# TPT02rrrrrr.net
KiCad netlist of a schematic drawn in EAGLE
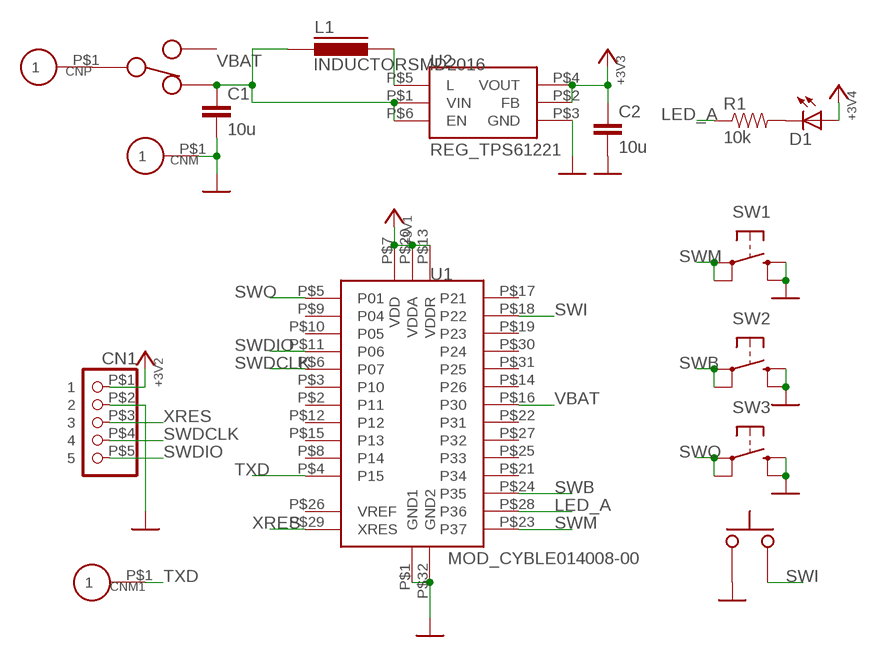
[diagram p0: schematic, sheet 1]

(export (version "E")
  (design (tool "Eeschema 10.0.6"))
  (components
    (comp (ref "C1")
      (value "10u")
      (footprint "eagle-import:0603")
      (libsource (lib "eagle-import") (part "CAP0603"))
    )
    (comp (ref "C2")
      (value "10u")
      (footprint "eagle-import:0603")
      (libsource (lib "eagle-import") (part "CAP0603"))
    )
    (comp (ref "CN1")
      (value "CON_PINHD-1X550MIL")
      (footprint "eagle-import:1X5_50MIL")
      (libsource (lib "eagle-import") (part "CON_PINHD-1X550MIL"))
    )
    (comp (ref "CNM")
      (value "CON_P01SMD1MM")
      (footprint "eagle-import:PAD_SMD1MM")
      (libsource (lib "eagle-import") (part "CON_P01SMD1MM"))
    )
    (comp (ref "CNM1")
      (value "CON_P01SMD1MM")
      (footprint "eagle-import:PAD_SMD1MM")
      (libsource (lib "eagle-import") (part "CON_P01SMD1MM"))
    )
    (comp (ref "CNP")
      (value "CON_P01SMD1MM")
      (footprint "eagle-import:PAD_SMD1MM")
      (libsource (lib "eagle-import") (part "CON_P01SMD1MM"))
    )
    (comp (ref "D1")
      (value "LED0603")
      (footprint "eagle-import:SPARKFUN_LED-0603")
      (libsource (lib "eagle-import") (part "LED0603"))
    )
    (comp (ref "L1")
      (value "INDUCTORSMD2016")
      (footprint "eagle-import:2016")
      (libsource (lib "eagle-import") (part "INDUCTORSMD2016"))
    )
    (comp (ref "R1")
      (value "10k")
      (footprint "eagle-import:0603")
      (libsource (lib "eagle-import") (part "RES0603"))
    )
    (comp (ref "SW1")
      (value "SW_TACTEVQP2")
      (footprint "eagle-import:SW_EVQP2")
      (libsource (lib "eagle-import") (part "SW_TACTEVQP2"))
    )
    (comp (ref "SW2")
      (value "SW_TACTEVQPLNA08NOGND")
      (footprint "eagle-import:SW_EVQPLBA08_NOGND")
      (libsource (lib "eagle-import") (part "SW_TACTEVQPLNA08NOGND"))
    )
    (comp (ref "SW3")
      (value "SW_TACTEVQPLNA08NOGND")
      (footprint "eagle-import:SW_EVQPLBA08_NOGND")
      (libsource (lib "eagle-import") (part "SW_TACTEVQPLNA08NOGND"))
    )
    (comp (ref "SW4")
      (value "SW_SLIDECUS12B")
      (footprint "eagle-import:SW_CUS-12B")
      (libsource (lib "eagle-import") (part "SW_SLIDECUS12B"))
    )
    (comp (ref "SW5")
      (value "SW_TACT2PB3U3000")
      (footprint "eagle-import:SW_B3U-3000P")
      (libsource (lib "eagle-import") (part "SW_TACT2PB3U3000"))
    )
    (comp (ref "U1")
      (value "MOD_CYBLE014008-00")
      (footprint "eagle-import:MOD_CYBLE014008-00")
      (libsource (lib "eagle-import") (part "MOD_CYBLE014008-00"))
    )
    (comp (ref "U2")
      (value "REG_TPS61221")
      (footprint "eagle-import:SC70-6")
      (libsource (lib "eagle-import") (part "REG_TPS61221"))
    )
  )
  (nets
    (net (code "1") (name "/LED_A") (class "Default")
      (node (ref "R1") (pin "1") (pinfunction "1_1") (pintype "passive"))
      (node (ref "U1") (pin "P$28") (pinfunction "P36_P$28") (pintype "bidirectional"))
    )
    (net (code "2") (name "/P$3") (class "Default")
      (node (ref "SW4") (pin "P$3") (pinfunction "P$3_P$3") (pintype "power_in"))
    )
    (net (code "3") (name "/SWB") (class "Default")
      (node (ref "SW2") (pin "A1") (pinfunction "P_A1") (pintype "passive"))
      (node (ref "SW2") (pin "A2") (pinfunction "P1_A2") (pintype "passive"))
      (node (ref "U1") (pin "P$24") (pinfunction "P35_P$24") (pintype "bidirectional"))
    )
    (net (code "4") (name "/SWDCLK") (class "Default")
      (node (ref "CN1") (pin "P$4") (pinfunction "4_P$4") (pintype "passive"))
      (node (ref "U1") (pin "P$6") (pinfunction "P07_P$6") (pintype "bidirectional"))
    )
    (net (code "5") (name "/SWDIO") (class "Default")
      (node (ref "CN1") (pin "P$5") (pinfunction "5_P$5") (pintype "passive"))
      (node (ref "U1") (pin "P$11") (pinfunction "P06_P$11") (pintype "bidirectional"))
    )
    (net (code "6") (name "/SWI") (class "Default")
      (node (ref "SW5") (pin "P$1") (pinfunction "P$1_P$1") (pintype "passive"))
      (node (ref "U1") (pin "P$18") (pinfunction "P22_P$18") (pintype "bidirectional"))
    )
    (net (code "7") (name "/SWM") (class "Default")
      (node (ref "SW1") (pin "PA1") (pinfunction "P_PA1") (pintype "passive"))
      (node (ref "SW1") (pin "PA2") (pinfunction "P1_PA2") (pintype "passive"))
      (node (ref "U1") (pin "P$23") (pinfunction "P37_P$23") (pintype "bidirectional"))
    )
    (net (code "8") (name "/SWO") (class "Default")
      (node (ref "SW3") (pin "A1") (pinfunction "P_A1") (pintype "passive"))
      (node (ref "SW3") (pin "A2") (pinfunction "P1_A2") (pintype "passive"))
      (node (ref "U1") (pin "P$5") (pinfunction "P01_P$5") (pintype "bidirectional"))
    )
    (net (code "9") (name "/TXD") (class "Default")
      (node (ref "CNM1") (pin "P$1") (pinfunction "1_P$1") (pintype "bidirectional"))
      (node (ref "U1") (pin "P$4") (pinfunction "P15_P$4") (pintype "bidirectional"))
    )
    (net (code "10") (name "/VBAT") (class "Default")
      (node (ref "C1") (pin "1") (pinfunction "1_1") (pintype "passive"))
      (node (ref "L1") (pin "P$1") (pinfunction "1_P$1") (pintype "passive"))
      (node (ref "SW4") (pin "P$1") (pinfunction "P$1_P$1") (pintype "power_in"))
      (node (ref "U1") (pin "P$16") (pinfunction "P30_P$16") (pintype "bidirectional"))
      (node (ref "U2") (pin "P$1") (pinfunction "VIN_P$1") (pintype "bidirectional"))
      (node (ref "U2") (pin "P$6") (pinfunction "EN_P$6") (pintype "bidirectional"))
    )
    (net (code "11") (name "/XRES") (class "Default")
      (node (ref "CN1") (pin "P$3") (pinfunction "3_P$3") (pintype "passive"))
      (node (ref "U1") (pin "P$29") (pinfunction "XRES_P$29") (pintype "bidirectional"))
    )
    (net (code "12") (name "Net-(CNP-1)") (class "Default")
      (node (ref "CNP") (pin "P$1") (pinfunction "1_P$1") (pintype "bidirectional"))
      (node (ref "SW4") (pin "P$2") (pinfunction "P$2_P$2") (pintype "power_in"))
    )
    (net (code "13") (name "Net-(D1-PadC)") (class "Default")
      (node (ref "D1") (pin "C") (pinfunction "C_C") (pintype "passive"))
      (node (ref "R1") (pin "2") (pinfunction "2_2") (pintype "passive"))
    )
    (net (code "14") (name "Net-(L1-2)") (class "Default")
      (node (ref "L1") (pin "P$2") (pinfunction "2_P$2") (pintype "passive"))
      (node (ref "U2") (pin "P$5") (pinfunction "L_P$5") (pintype "bidirectional"))
    )
    (net (code "15") (name "POW_+3V3") (class "Default")
      (node (ref "C2") (pin "1") (pinfunction "1_1") (pintype "passive"))
      (node (ref "CN1") (pin "P$1") (pinfunction "1_P$1") (pintype "passive"))
      (node (ref "D1") (pin "A") (pinfunction "A_A") (pintype "passive"))
      (node (ref "U1") (pin "P$13") (pinfunction "VDDR_P$13") (pintype "bidirectional"))
      (node (ref "U1") (pin "P$20") (pinfunction "VDDA_P$20") (pintype "bidirectional"))
      (node (ref "U1") (pin "P$7") (pinfunction "VDD_P$7") (pintype "bidirectional"))
      (node (ref "U2") (pin "P$2") (pinfunction "FB_P$2") (pintype "bidirectional"))
      (node (ref "U2") (pin "P$4") (pinfunction "VOUT_P$4") (pintype "bidirectional"))
    )
    (net (code "16") (name "POW_GND") (class "Default")
      (node (ref "C1") (pin "2") (pinfunction "2_2") (pintype "passive"))
      (node (ref "C2") (pin "2") (pinfunction "2_2") (pintype "passive"))
      (node (ref "CN1") (pin "P$2") (pinfunction "2_P$2") (pintype "passive"))
      (node (ref "CNM") (pin "P$1") (pinfunction "1_P$1") (pintype "bidirectional"))
      (node (ref "SW1") (pin "PB1") (pinfunction "S_PB1") (pintype "passive"))
      (node (ref "SW1") (pin "PB2") (pinfunction "S1_PB2") (pintype "passive"))
      (node (ref "SW2") (pin "B1") (pinfunction "S_B1") (pintype "passive"))
      (node (ref "SW2") (pin "B2") (pinfunction "S1_B2") (pintype "passive"))
      (node (ref "SW3") (pin "B1") (pinfunction "S_B1") (pintype "passive"))
      (node (ref "SW3") (pin "B2") (pinfunction "S1_B2") (pintype "passive"))
      (node (ref "SW5") (pin "P$2") (pinfunction "P$2_P$2") (pintype "passive"))
      (node (ref "U1") (pin "P$1") (pinfunction "GND1_P$1") (pintype "bidirectional"))
      (node (ref "U1") (pin "P$32") (pinfunction "GND2_P$32") (pintype "bidirectional"))
      (node (ref "U2") (pin "P$3") (pinfunction "GND_P$3") (pintype "bidirectional"))
    )
    (net (code "17") (name "unconnected-(U1-P04-PadP$9)") (class "Default")
      (node (ref "U1") (pin "P$9") (pinfunction "P04_P$9") (pintype "bidirectional"))
    )
    (net (code "18") (name "unconnected-(U1-P05-PadP$10)") (class "Default")
      (node (ref "U1") (pin "P$10") (pinfunction "P05_P$10") (pintype "bidirectional"))
    )
    (net (code "19") (name "unconnected-(U1-P10-PadP$3)") (class "Default")
      (node (ref "U1") (pin "P$3") (pinfunction "P10_P$3") (pintype "bidirectional"))
    )
    (net (code "20") (name "unconnected-(U1-P11-PadP$2)") (class "Default")
      (node (ref "U1") (pin "P$2") (pinfunction "P11_P$2") (pintype "bidirectional"))
    )
    (net (code "21") (name "unconnected-(U1-P12-PadP$12)") (class "Default")
      (node (ref "U1") (pin "P$12") (pinfunction "P12_P$12") (pintype "bidirectional"))
    )
    (net (code "22") (name "unconnected-(U1-P13-PadP$15)") (class "Default")
      (node (ref "U1") (pin "P$15") (pinfunction "P13_P$15") (pintype "bidirectional"))
    )
    (net (code "23") (name "unconnected-(U1-P14-PadP$8)") (class "Default")
      (node (ref "U1") (pin "P$8") (pinfunction "P14_P$8") (pintype "bidirectional"))
    )
    (net (code "24") (name "unconnected-(U1-P21-PadP$17)") (class "Default")
      (node (ref "U1") (pin "P$17") (pinfunction "P21_P$17") (pintype "bidirectional"))
    )
    (net (code "25") (name "unconnected-(U1-P23-PadP$19)") (class "Default")
      (node (ref "U1") (pin "P$19") (pinfunction "P23_P$19") (pintype "bidirectional"))
    )
    (net (code "26") (name "unconnected-(U1-P24-PadP$30)") (class "Default")
      (node (ref "U1") (pin "P$30") (pinfunction "P24_P$30") (pintype "bidirectional"))
    )
    (net (code "27") (name "unconnected-(U1-P25-PadP$31)") (class "Default")
      (node (ref "U1") (pin "P$31") (pinfunction "P25_P$31") (pintype "bidirectional"))
    )
    (net (code "28") (name "unconnected-(U1-P26-PadP$14)") (class "Default")
      (node (ref "U1") (pin "P$14") (pinfunction "P26_P$14") (pintype "bidirectional"))
    )
    (net (code "29") (name "unconnected-(U1-P31-PadP$22)") (class "Default")
      (node (ref "U1") (pin "P$22") (pinfunction "P31_P$22") (pintype "bidirectional"))
    )
    (net (code "30") (name "unconnected-(U1-P32-PadP$27)") (class "Default")
      (node (ref "U1") (pin "P$27") (pinfunction "P32_P$27") (pintype "bidirectional"))
    )
    (net (code "31") (name "unconnected-(U1-P33-PadP$25)") (class "Default")
      (node (ref "U1") (pin "P$25") (pinfunction "P33_P$25") (pintype "bidirectional"))
    )
    (net (code "32") (name "unconnected-(U1-P34-PadP$21)") (class "Default")
      (node (ref "U1") (pin "P$21") (pinfunction "P34_P$21") (pintype "bidirectional"))
    )
    (net (code "33") (name "unconnected-(U1-VREF-PadP$26)") (class "Default")
      (node (ref "U1") (pin "P$26") (pinfunction "VREF_P$26") (pintype "bidirectional"))
    )
  )
)
